# power_mux-v11.net
KiCad netlist of a schematic drawn in EAGLE
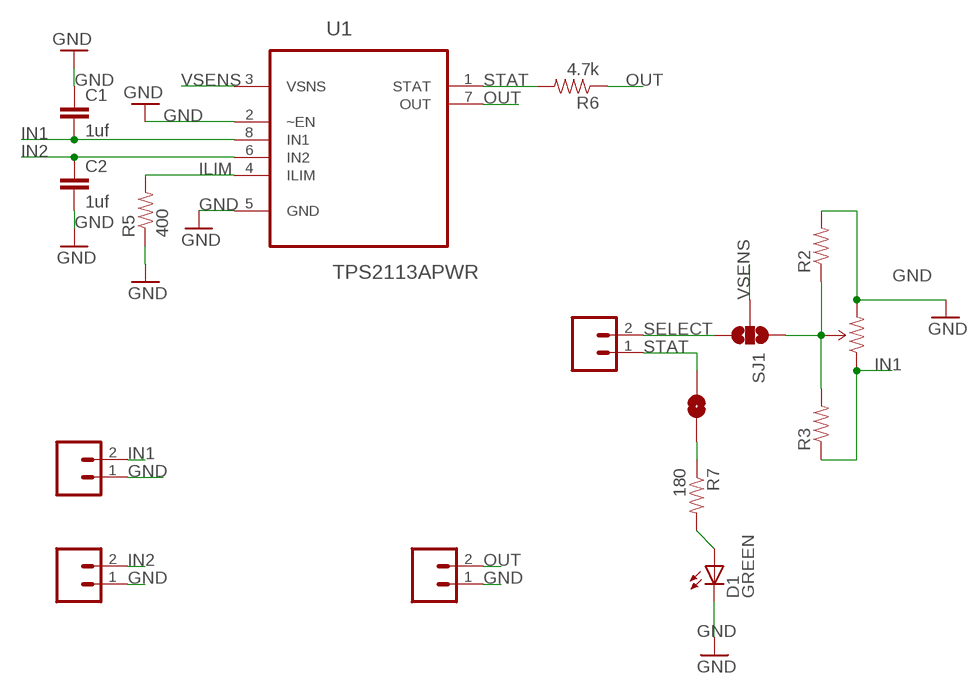
[diagram p0: schematic, sheet 1]

(export (version "E")
  (design (tool "Eeschema 10.0.6"))
  (components
    (comp (ref "C1")
      (value "1uf")
      (footprint "eagle-import:0603-CAP")
      (libsource (lib "eagle-import") (part "CAP0603-CAP"))
    )
    (comp (ref "C2")
      (value "1uf")
      (footprint "eagle-import:0603-CAP")
      (libsource (lib "eagle-import") (part "CAP0603-CAP"))
    )
    (comp (ref "D1")
      (value "GREEN")
      (footprint "eagle-import:LED-0603")
      (libsource (lib "eagle-import") (part "LED-GREEN0603"))
    )
    (comp (ref "JP3")
      (value "M021X02_NO_SILK")
      (footprint "eagle-import:1X02_NO_SILK")
      (libsource (lib "eagle-import") (part "M021X02_NO_SILK"))
    )
    (comp (ref "JP4")
      (value "M021X02_NO_SILK")
      (footprint "eagle-import:1X02_NO_SILK")
      (libsource (lib "eagle-import") (part "M021X02_NO_SILK"))
    )
    (comp (ref "JP5")
      (value "M021X02_NO_SILK")
      (footprint "eagle-import:1X02_NO_SILK")
      (libsource (lib "eagle-import") (part "M021X02_NO_SILK"))
    )
    (comp (ref "JP6")
      (value "M021X02_NO_SILK")
      (footprint "eagle-import:1X02_NO_SILK")
      (libsource (lib "eagle-import") (part "M021X02_NO_SILK"))
    )
    (comp (ref "R1")
      (value "TRIMPOT-PTH-KNOB")
      (footprint "eagle-import:3386U")
      (libsource (lib "eagle-import") (part "TRIMPOT-PTH-KNOB"))
    )
    (comp (ref "R2")
      (value "RESISTOR0603")
      (footprint "eagle-import:0603-RES")
      (libsource (lib "eagle-import") (part "RESISTOR0603"))
    )
    (comp (ref "R3")
      (value "RESISTOR0603")
      (footprint "eagle-import:0603-RES")
      (libsource (lib "eagle-import") (part "RESISTOR0603"))
    )
    (comp (ref "R5")
      (value "400")
      (footprint "eagle-import:0603-RES")
      (libsource (lib "eagle-import") (part "RESISTOR0603-RES"))
    )
    (comp (ref "R6")
      (value "4.7k")
      (footprint "eagle-import:0603-RES")
      (libsource (lib "eagle-import") (part "RESISTOR0603-RES"))
    )
    (comp (ref "R7")
      (value "180")
      (footprint "eagle-import:0603-RES")
      (libsource (lib "eagle-import") (part "RESISTOR0603-RES"))
    )
    (comp (ref "SJ1")
      (value "SOLDERJUMPER_2WAYPASTE1&2")
      (footprint "eagle-import:SJ_3_PASTE1&2")
      (libsource (lib "eagle-import") (part "SOLDERJUMPER_2WAYPASTE1&2"))
    )
    (comp (ref "SJ2")
      (value "SOLDERJUMPERNC2")
      (footprint "eagle-import:SJ_2S-NOTRACE")
      (libsource (lib "eagle-import") (part "SOLDERJUMPERNC2"))
    )
    (comp (ref "U1")
      (value "TPS2113APWR")
      (footprint "eagle-import:SOP65P640X120-8N")
      (libsource (lib "eagle-import") (part "TPS2113APWR"))
    )
  )
  (nets
    (net (code "1") (name "/ILIM") (class "Default")
      (node (ref "R5") (pin "2") (pinfunction "2_2") (pintype "passive"))
      (node (ref "U1") (pin "4") (pinfunction "ILIM_4") (pintype "input"))
    )
    (net (code "2") (name "/IN1") (class "Default")
      (node (ref "C1") (pin "2") (pinfunction "2_2") (pintype "passive"))
      (node (ref "JP3") (pin "2") (pinfunction "2_2") (pintype "passive"))
      (node (ref "R1") (pin "1") (pinfunction "CCW_1") (pintype "passive"))
      (node (ref "R3") (pin "1") (pinfunction "1_1") (pintype "passive"))
      (node (ref "U1") (pin "8") (pinfunction "IN1_8") (pintype "input"))
    )
    (net (code "3") (name "/IN2") (class "Default")
      (node (ref "C2") (pin "1") (pinfunction "1_1") (pintype "passive"))
      (node (ref "JP4") (pin "2") (pinfunction "2_2") (pintype "passive"))
      (node (ref "U1") (pin "6") (pinfunction "IN2_6") (pintype "input"))
    )
    (net (code "4") (name "/OUT") (class "Default")
      (node (ref "JP6") (pin "2") (pinfunction "2_2") (pintype "passive"))
      (node (ref "R6") (pin "1") (pinfunction "1_1") (pintype "passive"))
      (node (ref "U1") (pin "7") (pinfunction "OUT_7") (pintype "output"))
    )
    (net (code "5") (name "/SELECT") (class "Default")
      (node (ref "JP5") (pin "2") (pinfunction "2_2") (pintype "passive"))
      (node (ref "SJ1") (pin "3") (pinfunction "3_3") (pintype "passive"))
    )
    (net (code "6") (name "/STAT") (class "Default")
      (node (ref "JP5") (pin "1") (pinfunction "1_1") (pintype "passive"))
      (node (ref "R6") (pin "2") (pinfunction "2_2") (pintype "passive"))
      (node (ref "SJ2") (pin "2") (pinfunction "2_2") (pintype "passive"))
      (node (ref "U1") (pin "1") (pinfunction "STAT_1") (pintype "output"))
    )
    (net (code "7") (name "/VSENS") (class "Default")
      (node (ref "SJ1") (pin "2") (pinfunction "2_2") (pintype "passive"))
      (node (ref "U1") (pin "3") (pinfunction "VSNS_3") (pintype "power_in"))
    )
    (net (code "8") (name "GND") (class "Default")
      (node (ref "C1") (pin "1") (pinfunction "1_1") (pintype "passive"))
      (node (ref "C2") (pin "2") (pinfunction "2_2") (pintype "passive"))
      (node (ref "D1") (pin "C") (pinfunction "C_C") (pintype "passive"))
      (node (ref "JP3") (pin "1") (pinfunction "1_1") (pintype "passive"))
      (node (ref "JP4") (pin "1") (pinfunction "1_1") (pintype "passive"))
      (node (ref "JP6") (pin "1") (pinfunction "1_1") (pintype "passive"))
      (node (ref "R1") (pin "3") (pinfunction "CW_3") (pintype "passive"))
      (node (ref "R2") (pin "2") (pinfunction "2_2") (pintype "passive"))
      (node (ref "R5") (pin "1") (pinfunction "1_1") (pintype "passive"))
      (node (ref "U1") (pin "2") (pinfunction "~{EN}_2") (pintype "input"))
      (node (ref "U1") (pin "5") (pinfunction "GND_5") (pintype "passive"))
    )
    (net (code "9") (name "Net-(D1-PadA)") (class "Default")
      (node (ref "D1") (pin "A") (pinfunction "A_A") (pintype "passive"))
      (node (ref "R7") (pin "2") (pinfunction "2_2") (pintype "passive"))
    )
    (net (code "10") (name "Net-(R1-WIPER)") (class "Default")
      (node (ref "R1") (pin "2") (pinfunction "WIPER_2") (pintype "passive"))
      (node (ref "R2") (pin "1") (pinfunction "1_1") (pintype "passive"))
      (node (ref "R3") (pin "2") (pinfunction "2_2") (pintype "passive"))
      (node (ref "SJ1") (pin "1") (pinfunction "1_1") (pintype "passive"))
    )
    (net (code "11") (name "Net-(R7-Pad1)") (class "Default")
      (node (ref "R7") (pin "1") (pinfunction "1_1") (pintype "passive"))
      (node (ref "SJ2") (pin "1") (pinfunction "1_1") (pintype "passive"))
    )
  )
)
